# TDA2822M.net
KiCad netlist of a schematic drawn in EAGLE
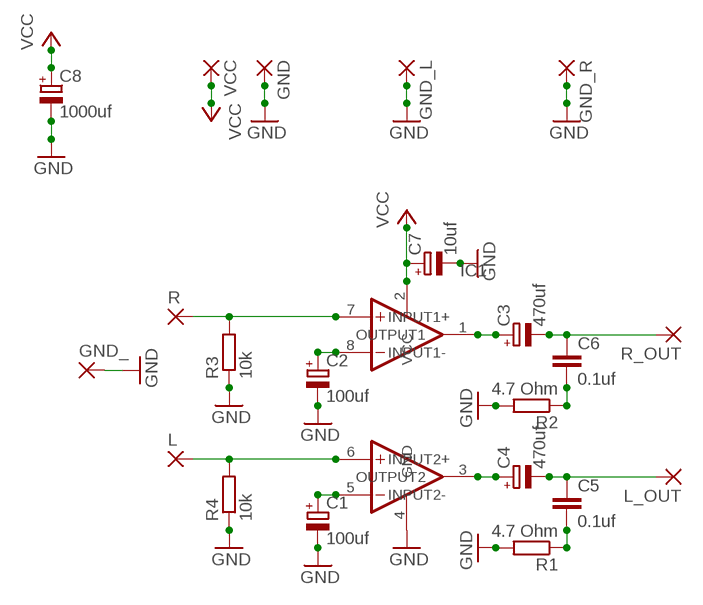
[diagram p0: schematic, sheet 1]

(export (version "E")
  (design (tool "Eeschema 10.0.6"))
  (components
    (comp (ref "C1")
      (value "100uf")
      (footprint "eagle-import:E2,5-6")
      (libsource (lib "eagle-import") (part "resistor_CPOL-EUE2.5-6"))
    )
    (comp (ref "C2")
      (value "100uf")
      (footprint "eagle-import:E2,5-6")
      (libsource (lib "eagle-import") (part "resistor_CPOL-EUE2.5-6"))
    )
    (comp (ref "C3")
      (value "470uf")
      (footprint "eagle-import:E2,5-6")
      (libsource (lib "eagle-import") (part "resistor_CPOL-EUE2.5-6"))
    )
    (comp (ref "C4")
      (value "470uf")
      (footprint "eagle-import:E2,5-6")
      (libsource (lib "eagle-import") (part "resistor_CPOL-EUE2.5-6"))
    )
    (comp (ref "C5")
      (value "0.1uf")
      (footprint "eagle-import:C025-030X050")
      (libsource (lib "eagle-import") (part "C-EU025-030X050"))
    )
    (comp (ref "C6")
      (value "0.1uf")
      (footprint "eagle-import:C025-030X050")
      (libsource (lib "eagle-import") (part "C-EU025-030X050"))
    )
    (comp (ref "C7")
      (value "10uf")
      (footprint "eagle-import:E2,5-6")
      (libsource (lib "eagle-import") (part "resistor_CPOL-EUE2.5-6"))
    )
    (comp (ref "C8")
      (value "1000uf")
      (footprint "eagle-import:E5-8,5")
      (libsource (lib "eagle-import") (part "CPOL-EUE5-8.5"))
    )
    (comp (ref "GND")
      (value "2,54/1,1")
      (footprint "eagle-import:2,54_1,1")
      (libsource (lib "eagle-import") (part "2,54/1,1"))
    )
    (comp (ref "GND_")
      (value "2,54/1,1")
      (footprint "eagle-import:2,54_1,1")
      (libsource (lib "eagle-import") (part "2,54/1,1"))
    )
    (comp (ref "GND_L")
      (value "2,54/1,1")
      (footprint "eagle-import:2,54_1,1")
      (libsource (lib "eagle-import") (part "2,54/1,1"))
    )
    (comp (ref "GND_R")
      (value "2,54/1,1")
      (footprint "eagle-import:2,54_1,1")
      (libsource (lib "eagle-import") (part "2,54/1,1"))
    )
    (comp (ref "IC1")
      (value "TDA2822M")
      (footprint "eagle-import:DIL8")
      (libsource (lib "eagle-import") (part "TDA2822M"))
    )
    (comp (ref "L")
      (value "2,54/1,1")
      (footprint "eagle-import:2,54_1,1")
      (libsource (lib "eagle-import") (part "2,54/1,1"))
    )
    (comp (ref "L_OUT")
      (value "2,54/1,1")
      (footprint "eagle-import:2,54_1,1")
      (libsource (lib "eagle-import") (part "2,54/1,1"))
    )
    (comp (ref "R")
      (value "2,54/1,1")
      (footprint "eagle-import:2,54_1,1")
      (libsource (lib "eagle-import") (part "2,54/1,1"))
    )
    (comp (ref "R1")
      (value "4.7 Ohm")
      (footprint "eagle-import:0204_7")
      (libsource (lib "eagle-import") (part "R-EU_0204/7"))
    )
    (comp (ref "R2")
      (value "4.7 Ohm")
      (footprint "eagle-import:0204_7")
      (libsource (lib "eagle-import") (part "R-EU_0204/7"))
    )
    (comp (ref "R3")
      (value "10k")
      (footprint "eagle-import:0204_7")
      (libsource (lib "eagle-import") (part "R-EU_0204/7"))
    )
    (comp (ref "R4")
      (value "10k")
      (footprint "eagle-import:0204_7")
      (libsource (lib "eagle-import") (part "R-EU_0204/7"))
    )
    (comp (ref "R_OUT")
      (value "2,54/1,1")
      (footprint "eagle-import:2,54_1,1")
      (libsource (lib "eagle-import") (part "2,54/1,1"))
    )
    (comp (ref "VCC")
      (value "2,54/1,1")
      (footprint "eagle-import:2,54_1,1")
      (libsource (lib "eagle-import") (part "2,54/1,1"))
    )
  )
  (nets
    (net (code "1") (name "GND") (class "Default")
      (node (ref "C1") (pin "-") (pinfunction "-_-") (pintype "passive"))
      (node (ref "C2") (pin "-") (pinfunction "-_-") (pintype "passive"))
      (node (ref "C7") (pin "-") (pinfunction "-_-") (pintype "passive"))
      (node (ref "C8") (pin "-") (pinfunction "-_-") (pintype "passive"))
      (node (ref "GND") (pin "1") (pinfunction "P_1") (pintype "passive"))
      (node (ref "GND_") (pin "1") (pinfunction "P_1") (pintype "passive"))
      (node (ref "GND_L") (pin "1") (pinfunction "P_1") (pintype "passive"))
      (node (ref "GND_R") (pin "1") (pinfunction "P_1") (pintype "passive"))
      (node (ref "IC1") (pin "4") (pinfunction "GND_4") (pintype "bidirectional"))
      (node (ref "R1") (pin "2") (pinfunction "2_2") (pintype "passive"))
      (node (ref "R2") (pin "2") (pinfunction "2_2") (pintype "passive"))
      (node (ref "R3") (pin "1") (pinfunction "1_1") (pintype "passive"))
      (node (ref "R4") (pin "1") (pinfunction "1_1") (pintype "passive"))
    )
    (net (code "2") (name "Net-(C5-Pad2)") (class "Default")
      (node (ref "C5") (pin "2") (pinfunction "2_2") (pintype "passive"))
      (node (ref "R1") (pin "1") (pinfunction "1_1") (pintype "passive"))
    )
    (net (code "3") (name "Net-(C6-Pad2)") (class "Default")
      (node (ref "C6") (pin "2") (pinfunction "2_2") (pintype "passive"))
      (node (ref "R2") (pin "1") (pinfunction "1_1") (pintype "passive"))
    )
    (net (code "4") (name "Net-(IC1-INPUT1+)") (class "Default")
      (node (ref "IC1") (pin "7") (pinfunction "INPUT1+_7") (pintype "bidirectional"))
      (node (ref "R") (pin "1") (pinfunction "P_1") (pintype "passive"))
      (node (ref "R3") (pin "2") (pinfunction "2_2") (pintype "passive"))
    )
    (net (code "5") (name "Net-(IC1-INPUT1-)") (class "Default")
      (node (ref "C2") (pin "+") (pinfunction "+_+") (pintype "passive"))
      (node (ref "IC1") (pin "8") (pinfunction "INPUT1-_8") (pintype "bidirectional"))
    )
    (net (code "6") (name "Net-(IC1-INPUT2+)") (class "Default")
      (node (ref "IC1") (pin "6") (pinfunction "INPUT2+_6") (pintype "bidirectional"))
      (node (ref "L") (pin "1") (pinfunction "P_1") (pintype "passive"))
      (node (ref "R4") (pin "2") (pinfunction "2_2") (pintype "passive"))
    )
    (net (code "7") (name "Net-(IC1-INPUT2-)") (class "Default")
      (node (ref "C1") (pin "+") (pinfunction "+_+") (pintype "passive"))
      (node (ref "IC1") (pin "5") (pinfunction "INPUT2-_5") (pintype "bidirectional"))
    )
    (net (code "8") (name "Net-(IC1-OUTPUT1)") (class "Default")
      (node (ref "C3") (pin "+") (pinfunction "+_+") (pintype "passive"))
      (node (ref "IC1") (pin "1") (pinfunction "OUTPUT1_1") (pintype "bidirectional"))
    )
    (net (code "9") (name "Net-(IC1-OUTPUT2)") (class "Default")
      (node (ref "C4") (pin "+") (pinfunction "+_+") (pintype "passive"))
      (node (ref "IC1") (pin "3") (pinfunction "OUTPUT2_3") (pintype "bidirectional"))
    )
    (net (code "10") (name "Net-(L_OUT-P)") (class "Default")
      (node (ref "C4") (pin "-") (pinfunction "-_-") (pintype "passive"))
      (node (ref "C5") (pin "1") (pinfunction "1_1") (pintype "passive"))
      (node (ref "L_OUT") (pin "1") (pinfunction "P_1") (pintype "passive"))
    )
    (net (code "11") (name "Net-(R_OUT-P)") (class "Default")
      (node (ref "C3") (pin "-") (pinfunction "-_-") (pintype "passive"))
      (node (ref "C6") (pin "1") (pinfunction "1_1") (pintype "passive"))
      (node (ref "R_OUT") (pin "1") (pinfunction "P_1") (pintype "passive"))
    )
    (net (code "12") (name "VCC") (class "Default")
      (node (ref "C7") (pin "+") (pinfunction "+_+") (pintype "passive"))
      (node (ref "C8") (pin "+") (pinfunction "+_+") (pintype "passive"))
      (node (ref "IC1") (pin "2") (pinfunction "VCC_2") (pintype "bidirectional"))
      (node (ref "VCC") (pin "1") (pinfunction "P_1") (pintype "passive"))
    )
  )
)
